# Si470x-Eval.net
KiCad netlist of a schematic drawn in EAGLE
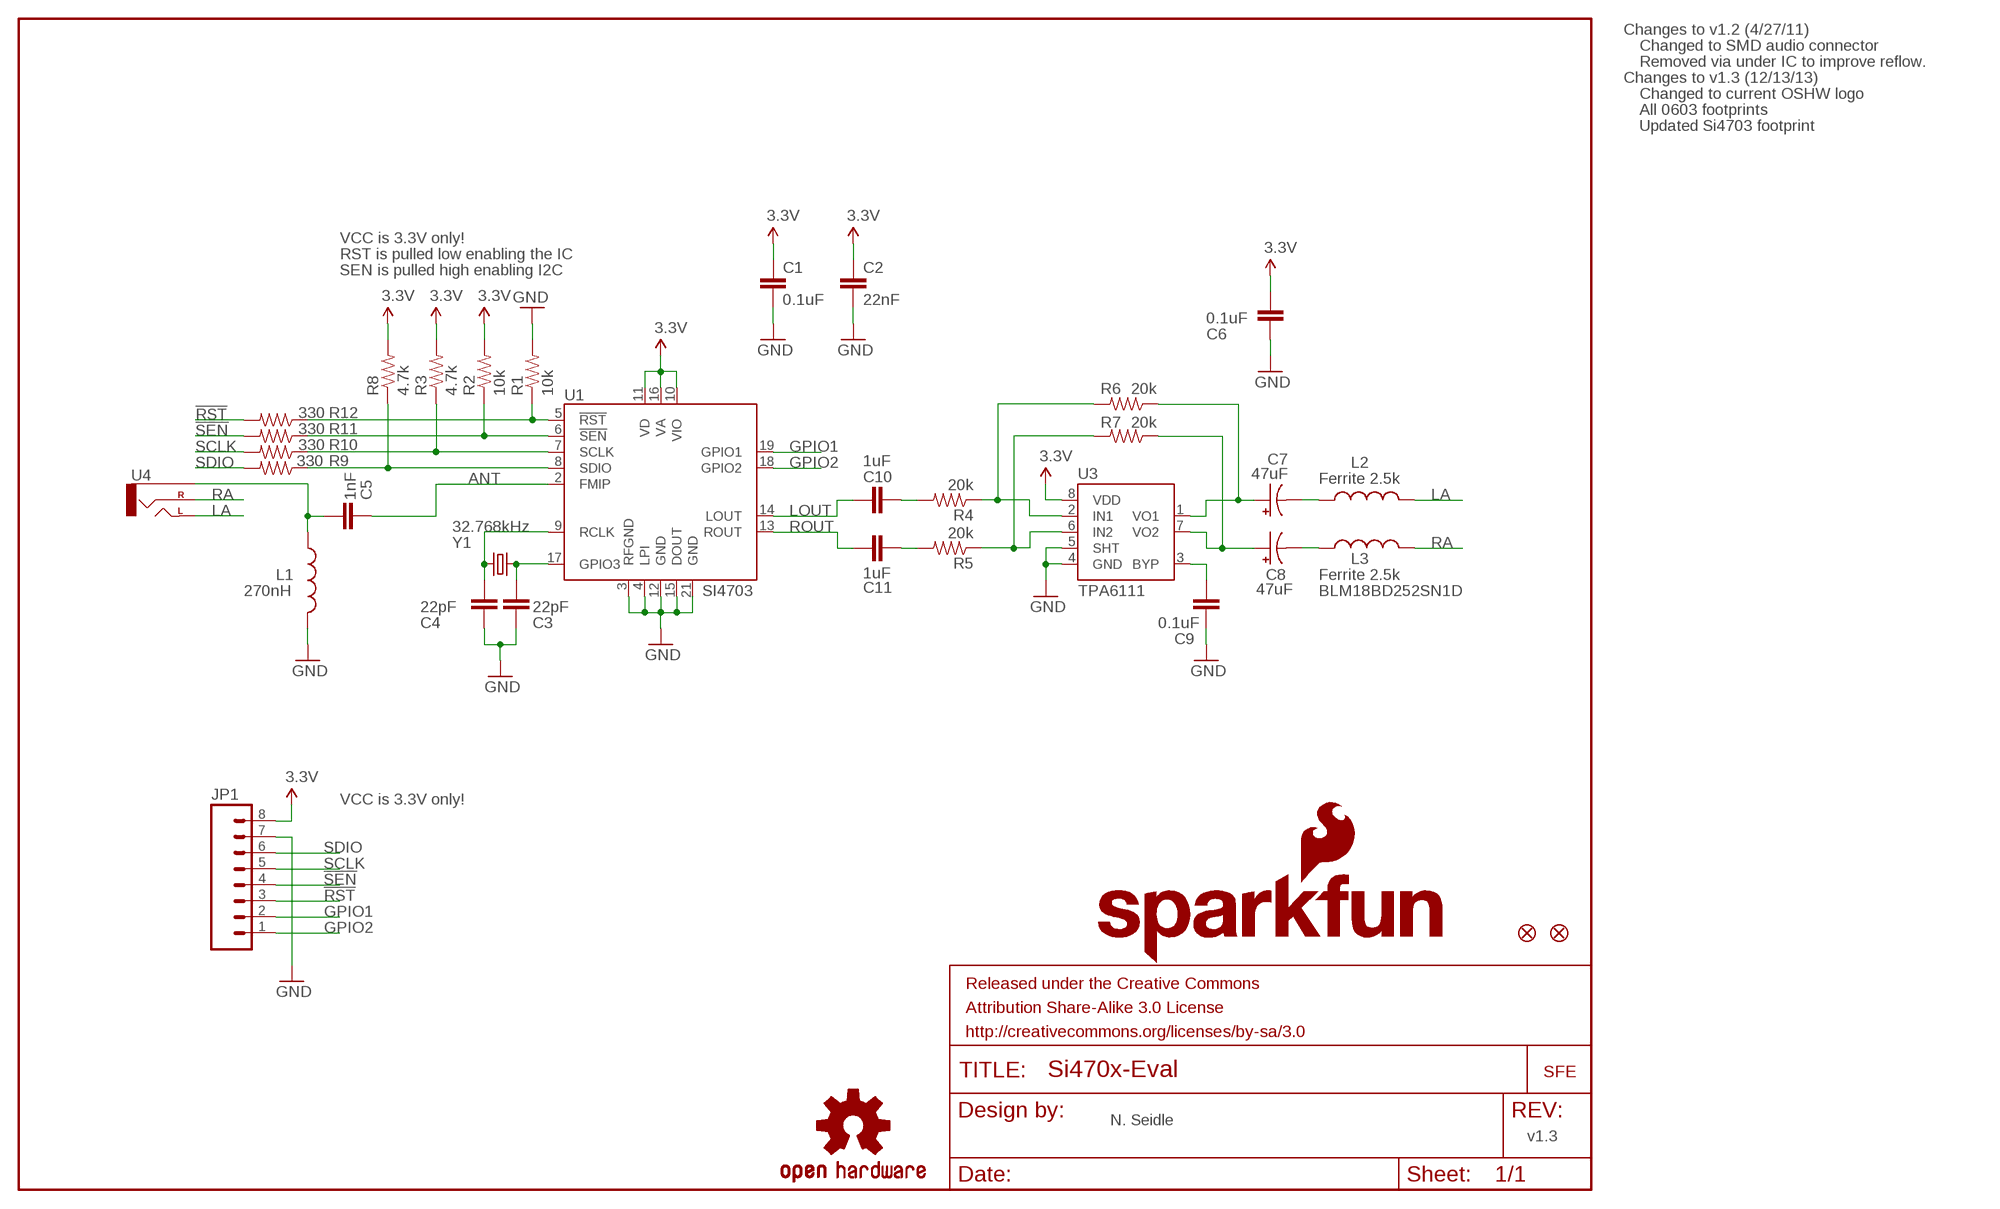
[diagram p0: schematic, sheet 1]

(export (version "E")
  (design (tool "Eeschema 10.0.6"))
  (components
    (comp (ref "C1")
      (value "0.1uF")
      (footprint "eagle-import:0603-CAP")
      (libsource (lib "eagle-import") (part "0.1UF-25V(+80/-20%)(0603)"))
    )
    (comp (ref "C2")
      (value "22nF")
      (footprint "eagle-import:0603-CAP")
      (libsource (lib "eagle-import") (part "22NF/22,000PF-50V-10%(0603)"))
    )
    (comp (ref "C3")
      (value "22pF")
      (footprint "eagle-import:0603-CAP")
      (libsource (lib "eagle-import") (part "22PF-50V-5%(0603)"))
    )
    (comp (ref "C4")
      (value "22pF")
      (footprint "eagle-import:0603-CAP")
      (libsource (lib "eagle-import") (part "22PF-50V-5%(0603)"))
    )
    (comp (ref "C5")
      (value "1nF")
      (footprint "eagle-import:0603-CAP")
      (libsource (lib "eagle-import") (part "1NF/1000PF-50V-10%(0603)"))
    )
    (comp (ref "C6")
      (value "0.1uF")
      (footprint "eagle-import:0603-CAP")
      (libsource (lib "eagle-import") (part "0.1UF-25V(+80/-20%)(0603)"))
    )
    (comp (ref "C7")
      (value "47uF")
      (footprint "eagle-import:EIA3528")
      (libsource (lib "eagle-import") (part "47UF-TANT"))
    )
    (comp (ref "C8")
      (value "47uF")
      (footprint "eagle-import:EIA3528")
      (libsource (lib "eagle-import") (part "47UF-TANT"))
    )
    (comp (ref "C9")
      (value "0.1uF")
      (footprint "eagle-import:0603-CAP")
      (libsource (lib "eagle-import") (part "0.1UF-25V(+80/-20%)(0603)"))
    )
    (comp (ref "C10")
      (value "1uF")
      (footprint "eagle-import:0603-CAP")
      (libsource (lib "eagle-import") (part "1.0UF-16V-10%(0603)"))
    )
    (comp (ref "C11")
      (value "1uF")
      (footprint "eagle-import:0603-CAP")
      (libsource (lib "eagle-import") (part "1.0UF-16V-10%(0603)"))
    )
    (comp (ref "FRAME2")
      (value "FRAME-LETTER")
      (footprint "eagle-import:CREATIVE_COMMONS")
      (libsource (lib "eagle-import") (part "FRAME-LETTER"))
    )
    (comp (ref "JP1")
      (value "M08")
      (footprint "eagle-import:1X08")
      (libsource (lib "eagle-import") (part "M08"))
    )
    (comp (ref "JP3")
      (value "LOGO-SFESK")
      (footprint "eagle-import:SFE-LOGO-FLAME")
      (libsource (lib "eagle-import") (part "LOGO-SFESK"))
    )
    (comp (ref "JP4")
      (value "FIDUCIAL1X2")
      (footprint "eagle-import:FIDUCIAL-1X2")
      (libsource (lib "eagle-import") (part "FIDUCIAL1X2"))
    )
    (comp (ref "JP5")
      (value "FIDUCIAL1X2")
      (footprint "eagle-import:FIDUCIAL-1X2")
      (libsource (lib "eagle-import") (part "FIDUCIAL1X2"))
    )
    (comp (ref "L1")
      (value "270nH")
      (footprint "eagle-import:0603")
      (libsource (lib "eagle-import") (part "INDUCTOR0603"))
    )
    (comp (ref "L2")
      (value "Ferrite 2.5k")
      (footprint "eagle-import:0603")
      (libsource (lib "eagle-import") (part "INDUCTOR0603"))
    )
    (comp (ref "L3")
      (value "Ferrite 2.5k")
      (footprint "eagle-import:0603")
      (libsource (lib "eagle-import") (part "INDUCTOR0603"))
    )
    (comp (ref "LOGO1")
      (value "SFE_LOGO_NAME_FLAME.1_INCH")
      (footprint "eagle-import:SFE_LOGO_NAME_FLAME_.1")
      (libsource (lib "eagle-import") (part "SFE_LOGO_NAME_FLAME.1_INCH"))
    )
    (comp (ref "LOGO2")
      (value "OSHW-LOGOS")
      (footprint "eagle-import:OSHW-LOGO-S")
      (libsource (lib "eagle-import") (part "OSHW-LOGOS"))
    )
    (comp (ref "R1")
      (value "10k")
      (footprint "eagle-import:0603-RES")
      (libsource (lib "eagle-import") (part "10KOHM1/10W1%(0603)0603"))
    )
    (comp (ref "R2")
      (value "10k")
      (footprint "eagle-import:0603-RES")
      (libsource (lib "eagle-import") (part "10KOHM1/10W1%(0603)0603"))
    )
    (comp (ref "R3")
      (value "4.7k")
      (footprint "eagle-import:0603")
      (libsource (lib "eagle-import") (part "4.7KOHM1/10W1%(0603)"))
    )
    (comp (ref "R4")
      (value "20k")
      (footprint "eagle-import:0603-RES")
      (libsource (lib "eagle-import") (part "20KOHM1/10W1%(0603)"))
    )
    (comp (ref "R5")
      (value "20k")
      (footprint "eagle-import:0603-RES")
      (libsource (lib "eagle-import") (part "20KOHM1/10W1%(0603)"))
    )
    (comp (ref "R6")
      (value "20k")
      (footprint "eagle-import:0603-RES")
      (libsource (lib "eagle-import") (part "20KOHM1/10W1%(0603)"))
    )
    (comp (ref "R7")
      (value "20k")
      (footprint "eagle-import:0603-RES")
      (libsource (lib "eagle-import") (part "20KOHM1/10W1%(0603)"))
    )
    (comp (ref "R8")
      (value "4.7k")
      (footprint "eagle-import:0603")
      (libsource (lib "eagle-import") (part "4.7KOHM1/10W1%(0603)"))
    )
    (comp (ref "R9")
      (value "330")
      (footprint "eagle-import:0603-RES")
      (libsource (lib "eagle-import") (part "330OHM1/10W1%(0603)"))
    )
    (comp (ref "R10")
      (value "330")
      (footprint "eagle-import:0603-RES")
      (libsource (lib "eagle-import") (part "330OHM1/10W1%(0603)"))
    )
    (comp (ref "R11")
      (value "330")
      (footprint "eagle-import:0603-RES")
      (libsource (lib "eagle-import") (part "330OHM1/10W1%(0603)"))
    )
    (comp (ref "R12")
      (value "330")
      (footprint "eagle-import:0603-RES")
      (libsource (lib "eagle-import") (part "330OHM1/10W1%(0603)"))
    )
    (comp (ref "U1")
      (value "SI4703")
      (footprint "eagle-import:SI470X")
      (libsource (lib "eagle-import") (part "SI470X"))
    )
    (comp (ref "U3")
      (value "TPA6111")
      (footprint "eagle-import:SO08-TIGHT")
      (libsource (lib "eagle-import") (part "TPA6111SMD-T"))
    )
    (comp (ref "U4")
      (value "AUDIO-JACKSMD2")
      (footprint "eagle-import:AUDIO-JACK-3.5MM-SMD")
      (libsource (lib "eagle-import") (part "AUDIO-JACKSMD2"))
    )
    (comp (ref "Y1")
      (value "32.768kHz")
      (footprint "eagle-import:CRYSTAL-32KHZ-SMD")
      (libsource (lib "eagle-import") (part "CRYSTAL32-SMD"))
    )
  )
  (nets
    (net (code "1") (name "/ANT") (class "Default")
      (node (ref "C5") (pin "1") (pinfunction "1_1") (pintype "passive"))
      (node (ref "U1") (pin "2") (pinfunction "FMIP_2") (pintype "bidirectional"))
    )
    (net (code "2") (name "/GPIO1") (class "Default")
      (node (ref "JP1") (pin "2") (pinfunction "2_2") (pintype "passive"))
      (node (ref "U1") (pin "19") (pinfunction "GPIO1_19") (pintype "bidirectional"))
    )
    (net (code "3") (name "/GPIO2") (class "Default")
      (node (ref "JP1") (pin "1") (pinfunction "1_1") (pintype "passive"))
      (node (ref "U1") (pin "18") (pinfunction "GPIO2_18") (pintype "bidirectional"))
    )
    (net (code "4") (name "/LA") (class "Default")
      (node (ref "L2") (pin "2") (pinfunction "2_2") (pintype "passive"))
      (node (ref "U4") (pin "TIP") (pinfunction "LEFT_TIP") (pintype "bidirectional"))
    )
    (net (code "5") (name "/LOUT") (class "Default")
      (node (ref "C10") (pin "1") (pinfunction "1_1") (pintype "passive"))
      (node (ref "U1") (pin "14") (pinfunction "LOUT_14") (pintype "bidirectional"))
    )
    (net (code "6") (name "/RA") (class "Default")
      (node (ref "L3") (pin "2") (pinfunction "2_2") (pintype "passive"))
      (node (ref "U4") (pin "RING") (pinfunction "RIGHT_RING") (pintype "bidirectional"))
    )
    (net (code "7") (name "/ROUT") (class "Default")
      (node (ref "C11") (pin "1") (pinfunction "1_1") (pintype "passive"))
      (node (ref "U1") (pin "13") (pinfunction "ROUT_13") (pintype "bidirectional"))
    )
    (net (code "8") (name "/SCLK") (class "Default")
      (node (ref "JP1") (pin "5") (pinfunction "5_5") (pintype "passive"))
      (node (ref "R10") (pin "2") (pinfunction "2_2") (pintype "passive"))
    )
    (net (code "9") (name "/SDIO") (class "Default")
      (node (ref "JP1") (pin "6") (pinfunction "6_6") (pintype "passive"))
      (node (ref "R9") (pin "2") (pinfunction "2_2") (pintype "passive"))
    )
    (net (code "10") (name "/~{RST}") (class "Default")
      (node (ref "JP1") (pin "3") (pinfunction "3_3") (pintype "passive"))
      (node (ref "R12") (pin "2") (pinfunction "2_2") (pintype "passive"))
    )
    (net (code "11") (name "/~{SEN}") (class "Default")
      (node (ref "JP1") (pin "4") (pinfunction "4_4") (pintype "passive"))
      (node (ref "R11") (pin "2") (pinfunction "2_2") (pintype "passive"))
    )
    (net (code "12") (name "3.3V") (class "Default")
      (node (ref "C1") (pin "1") (pinfunction "1_1") (pintype "passive"))
      (node (ref "C2") (pin "1") (pinfunction "1_1") (pintype "passive"))
      (node (ref "C6") (pin "2") (pinfunction "2_2") (pintype "passive"))
      (node (ref "JP1") (pin "8") (pinfunction "8_8") (pintype "passive"))
      (node (ref "R2") (pin "2") (pinfunction "2_2") (pintype "passive"))
      (node (ref "R3") (pin "2") (pinfunction "2_2") (pintype "passive"))
      (node (ref "R8") (pin "2") (pinfunction "2_2") (pintype "passive"))
      (node (ref "U1") (pin "10") (pinfunction "VIO_10") (pintype "bidirectional"))
      (node (ref "U1") (pin "11") (pinfunction "VD_11") (pintype "bidirectional"))
      (node (ref "U1") (pin "16") (pinfunction "VA_16") (pintype "bidirectional"))
      (node (ref "U3") (pin "8") (pinfunction "VDD_8") (pintype "bidirectional"))
    )
    (net (code "13") (name "GND") (class "Default")
      (node (ref "C1") (pin "2") (pinfunction "2_2") (pintype "passive"))
      (node (ref "C2") (pin "2") (pinfunction "2_2") (pintype "passive"))
      (node (ref "C3") (pin "1") (pinfunction "1_1") (pintype "passive"))
      (node (ref "C4") (pin "1") (pinfunction "1_1") (pintype "passive"))
      (node (ref "C6") (pin "1") (pinfunction "1_1") (pintype "passive"))
      (node (ref "C9") (pin "2") (pinfunction "2_2") (pintype "passive"))
      (node (ref "JP1") (pin "7") (pinfunction "7_7") (pintype "passive"))
      (node (ref "L1") (pin "2") (pinfunction "2_2") (pintype "passive"))
      (node (ref "R1") (pin "2") (pinfunction "2_2") (pintype "passive"))
      (node (ref "U1") (pin "12") (pinfunction "GND_12") (pintype "bidirectional"))
      (node (ref "U1") (pin "15") (pinfunction "DOUT_15") (pintype "bidirectional"))
      (node (ref "U1") (pin "21") (pinfunction "GND_21") (pintype "bidirectional"))
      (node (ref "U1") (pin "3") (pinfunction "RFGND_3") (pintype "bidirectional"))
      (node (ref "U1") (pin "4") (pinfunction "LPI_4") (pintype "bidirectional"))
      (node (ref "U3") (pin "4") (pinfunction "GND_4") (pintype "bidirectional"))
      (node (ref "U3") (pin "5") (pinfunction "SHT_5") (pintype "bidirectional"))
    )
    (net (code "14") (name "Net-(C5-Pad2)") (class "Default")
      (node (ref "C5") (pin "2") (pinfunction "2_2") (pintype "passive"))
      (node (ref "L1") (pin "1") (pinfunction "1_1") (pintype "passive"))
      (node (ref "U4") (pin "SLEEVE") (pinfunction "SLEEVE_SLEEVE") (pintype "bidirectional"))
    )
    (net (code "15") (name "Net-(C7-+)") (class "Default")
      (node (ref "C7") (pin "A") (pinfunction "+_A") (pintype "passive"))
      (node (ref "R6") (pin "1") (pinfunction "1_1") (pintype "passive"))
      (node (ref "U3") (pin "1") (pinfunction "VO1_1") (pintype "bidirectional"))
    )
    (net (code "16") (name "Net-(C7--)") (class "Default")
      (node (ref "C7") (pin "C") (pinfunction "-_C") (pintype "passive"))
      (node (ref "L2") (pin "1") (pinfunction "1_1") (pintype "passive"))
    )
    (net (code "17") (name "Net-(C8-+)") (class "Default")
      (node (ref "C8") (pin "A") (pinfunction "+_A") (pintype "passive"))
      (node (ref "R7") (pin "1") (pinfunction "1_1") (pintype "passive"))
      (node (ref "U3") (pin "7") (pinfunction "VO2_7") (pintype "bidirectional"))
    )
    (net (code "18") (name "Net-(C8--)") (class "Default")
      (node (ref "C8") (pin "C") (pinfunction "-_C") (pintype "passive"))
      (node (ref "L3") (pin "1") (pinfunction "1_1") (pintype "passive"))
    )
    (net (code "19") (name "Net-(C10-Pad2)") (class "Default")
      (node (ref "C10") (pin "2") (pinfunction "2_2") (pintype "passive"))
      (node (ref "R4") (pin "2") (pinfunction "2_2") (pintype "passive"))
    )
    (net (code "20") (name "Net-(C11-Pad2)") (class "Default")
      (node (ref "C11") (pin "2") (pinfunction "2_2") (pintype "passive"))
      (node (ref "R5") (pin "2") (pinfunction "2_2") (pintype "passive"))
    )
    (net (code "21") (name "Net-(U1-GPIO3)") (class "Default")
      (node (ref "C3") (pin "2") (pinfunction "2_2") (pintype "passive"))
      (node (ref "U1") (pin "17") (pinfunction "GPIO3_17") (pintype "bidirectional"))
      (node (ref "Y1") (pin "X1") (pinfunction "1_X1") (pintype "passive"))
    )
    (net (code "22") (name "Net-(U1-RCLK)") (class "Default")
      (node (ref "C4") (pin "2") (pinfunction "2_2") (pintype "passive"))
      (node (ref "U1") (pin "9") (pinfunction "RCLK_9") (pintype "bidirectional"))
      (node (ref "Y1") (pin "X2") (pinfunction "2_X2") (pintype "passive"))
    )
    (net (code "23") (name "Net-(U1-SCLK)") (class "Default")
      (node (ref "R10") (pin "1") (pinfunction "1_1") (pintype "passive"))
      (node (ref "R3") (pin "1") (pinfunction "1_1") (pintype "passive"))
      (node (ref "U1") (pin "7") (pinfunction "SCLK_7") (pintype "bidirectional"))
    )
    (net (code "24") (name "Net-(U1-SDIO)") (class "Default")
      (node (ref "R8") (pin "1") (pinfunction "1_1") (pintype "passive"))
      (node (ref "R9") (pin "1") (pinfunction "1_1") (pintype "passive"))
      (node (ref "U1") (pin "8") (pinfunction "SDIO_8") (pintype "bidirectional"))
    )
    (net (code "25") (name "Net-(U1-~{RST})") (class "Default")
      (node (ref "R1") (pin "1") (pinfunction "1_1") (pintype "passive"))
      (node (ref "R12") (pin "1") (pinfunction "1_1") (pintype "passive"))
      (node (ref "U1") (pin "5") (pinfunction "~{RST}_5") (pintype "bidirectional"))
    )
    (net (code "26") (name "Net-(U1-~{SEN})") (class "Default")
      (node (ref "R11") (pin "1") (pinfunction "1_1") (pintype "passive"))
      (node (ref "R2") (pin "1") (pinfunction "1_1") (pintype "passive"))
      (node (ref "U1") (pin "6") (pinfunction "~{SEN}_6") (pintype "bidirectional"))
    )
    (net (code "27") (name "Net-(U3-BYP)") (class "Default")
      (node (ref "C9") (pin "1") (pinfunction "1_1") (pintype "passive"))
      (node (ref "U3") (pin "3") (pinfunction "BYP_3") (pintype "bidirectional"))
    )
    (net (code "28") (name "Net-(U3-IN1)") (class "Default")
      (node (ref "R4") (pin "1") (pinfunction "1_1") (pintype "passive"))
      (node (ref "R6") (pin "2") (pinfunction "2_2") (pintype "passive"))
      (node (ref "U3") (pin "2") (pinfunction "IN1_2") (pintype "bidirectional"))
    )
    (net (code "29") (name "Net-(U3-IN2)") (class "Default")
      (node (ref "R5") (pin "1") (pinfunction "1_1") (pintype "passive"))
      (node (ref "R7") (pin "2") (pinfunction "2_2") (pintype "passive"))
      (node (ref "U3") (pin "6") (pinfunction "IN2_6") (pintype "bidirectional"))
    )
  )
)
